# ORIONRP2350.net
KiCad netlist of a schematic drawn in EasyEDA
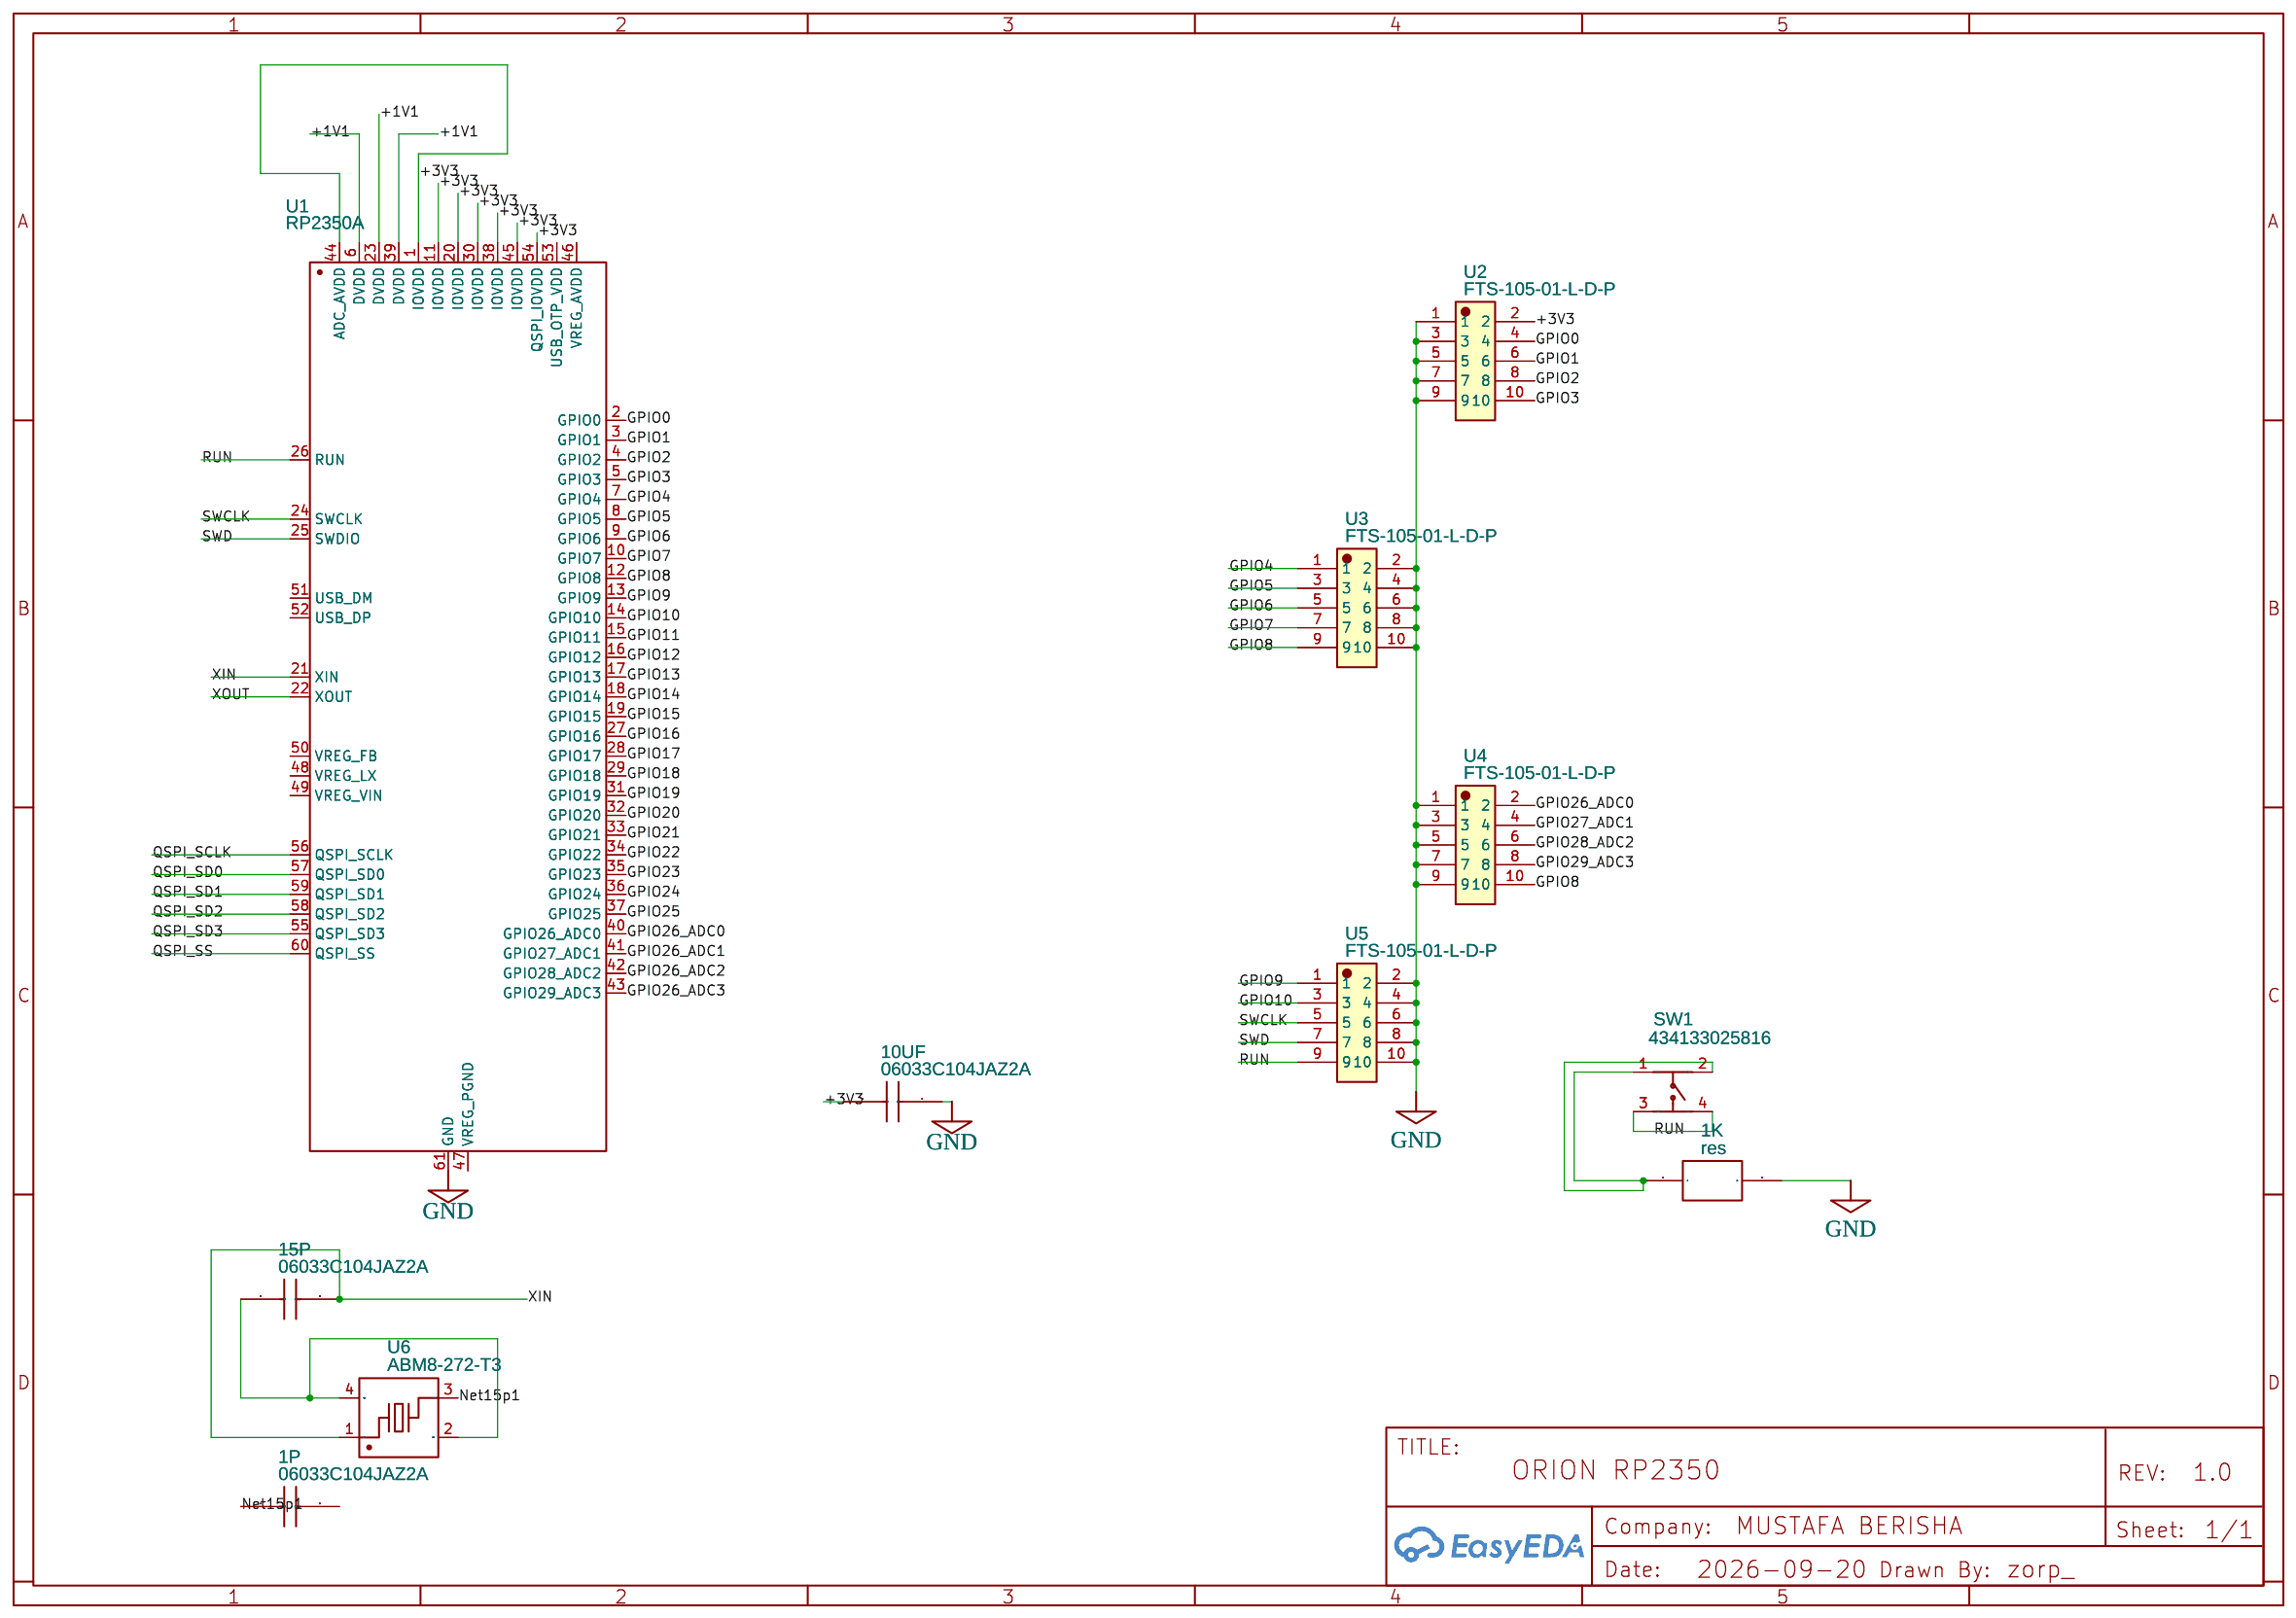
[diagram p0: schematic sheet]

(export (version "E")
  (design (tool "Eeschema 10.0.6"))
  (components
    (comp (ref "1K") (value "res") (libsource (lib "") (part "res")))
    (comp (ref "1P") (value "06033C104JAZ2A") (libsource (lib "") (part "06033C104JAZ2A")))
    (comp (ref "10UF") (value "06033C104JAZ2A") (libsource (lib "") (part "06033C104JAZ2A_1")))
    (comp (ref "15P") (value "06033C104JAZ2A") (libsource (lib "") (part "06033C104JAZ2A_2")))
    (comp (ref "SW1")
      (value "434133025816")
      (fields (field (name "Manufacturer") "Wurth(伍尔特)"))
      (libsource (lib "") (part "434133025816"))
    )
    (comp (ref "U1") (value "RP2350A") (libsource (lib "") (part "RP2350A")))
    (comp (ref "U2") (value "FTS-105-01-L-D-P") (libsource (lib "") (part "FTS-105-01-L-D-P")))
    (comp (ref "U3") (value "FTS-105-01-L-D-P") (libsource (lib "") (part "FTS-105-01-L-D-P")))
    (comp (ref "U4") (value "FTS-105-01-L-D-P") (libsource (lib "") (part "FTS-105-01-L-D-P")))
    (comp (ref "U5") (value "FTS-105-01-L-D-P") (libsource (lib "") (part "FTS-105-01-L-D-P")))
    (comp (ref "U6") (value "ABM8-272-T3") (libsource (lib "") (part "ABM8-272-T3")))
  )
  (nets
    (net (code "1") (name "/+1V1") (class "Default")
      (node (ref "U1") (pin "23") (pinfunction "DVDD_23") (pintype "unspecified"))
      (node (ref "U1") (pin "39") (pinfunction "DVDD_39") (pintype "unspecified"))
      (node (ref "U1") (pin "6") (pinfunction "DVDD_6") (pintype "unspecified"))
    )
    (net (code "2") (name "/+3V3") (class "Default")
      (node (ref "10UF") (pin "1") (pinfunction "1_1") (pintype "unspecified"))
      (node (ref "U1") (pin "1") (pinfunction "IOVDD_1") (pintype "unspecified"))
      (node (ref "U1") (pin "11") (pinfunction "IOVDD_11") (pintype "unspecified"))
      (node (ref "U1") (pin "20") (pinfunction "IOVDD_20") (pintype "unspecified"))
      (node (ref "U1") (pin "30") (pinfunction "IOVDD_30") (pintype "unspecified"))
      (node (ref "U1") (pin "38") (pinfunction "IOVDD_38") (pintype "unspecified"))
      (node (ref "U1") (pin "44") (pinfunction "ADC_AVDD_44") (pintype "unspecified"))
      (node (ref "U1") (pin "45") (pinfunction "IOVDD_45") (pintype "unspecified"))
      (node (ref "U1") (pin "54") (pinfunction "QSPI_IOVDD_54") (pintype "unspecified"))
      (node (ref "U2") (pin "2") (pinfunction "2_2") (pintype "unspecified"))
    )
    (net (code "3") (name "/GPIO0") (class "Default")
      (node (ref "U1") (pin "2") (pinfunction "GPIO0_2") (pintype "unspecified"))
      (node (ref "U2") (pin "4") (pinfunction "4_4") (pintype "unspecified"))
    )
    (net (code "4") (name "/GPIO1") (class "Default")
      (node (ref "U1") (pin "3") (pinfunction "GPIO1_3") (pintype "unspecified"))
      (node (ref "U2") (pin "6") (pinfunction "6_6") (pintype "unspecified"))
    )
    (net (code "5") (name "/GPIO2") (class "Default")
      (node (ref "U1") (pin "4") (pinfunction "GPIO2_4") (pintype "unspecified"))
      (node (ref "U2") (pin "8") (pinfunction "8_8") (pintype "unspecified"))
    )
    (net (code "6") (name "/GPIO3") (class "Default")
      (node (ref "U1") (pin "5") (pinfunction "GPIO3_5") (pintype "unspecified"))
      (node (ref "U2") (pin "10") (pinfunction "10_10") (pintype "unspecified"))
    )
    (net (code "7") (name "/GPIO4") (class "Default")
      (node (ref "U1") (pin "7") (pinfunction "GPIO4_7") (pintype "unspecified"))
      (node (ref "U3") (pin "1") (pinfunction "1_1") (pintype "unspecified"))
    )
    (net (code "8") (name "/GPIO5") (class "Default")
      (node (ref "U1") (pin "8") (pinfunction "GPIO5_8") (pintype "unspecified"))
      (node (ref "U3") (pin "3") (pinfunction "3_3") (pintype "unspecified"))
    )
    (net (code "9") (name "/GPIO6") (class "Default")
      (node (ref "U1") (pin "9") (pinfunction "GPIO6_9") (pintype "unspecified"))
      (node (ref "U3") (pin "5") (pinfunction "5_5") (pintype "unspecified"))
    )
    (net (code "10") (name "/GPIO7") (class "Default")
      (node (ref "U1") (pin "10") (pinfunction "GPIO7_10") (pintype "unspecified"))
      (node (ref "U3") (pin "7") (pinfunction "7_7") (pintype "unspecified"))
    )
    (net (code "11") (name "/GPIO8") (class "Default")
      (node (ref "U1") (pin "12") (pinfunction "GPIO8_12") (pintype "unspecified"))
      (node (ref "U3") (pin "9") (pinfunction "9_9") (pintype "unspecified"))
      (node (ref "U4") (pin "10") (pinfunction "10_10") (pintype "unspecified"))
    )
    (net (code "12") (name "/GPIO9") (class "Default")
      (node (ref "U1") (pin "13") (pinfunction "GPIO9_13") (pintype "unspecified"))
      (node (ref "U5") (pin "1") (pinfunction "1_1") (pintype "unspecified"))
    )
    (net (code "13") (name "/GPIO10") (class "Default")
      (node (ref "U1") (pin "14") (pinfunction "GPIO10_14") (pintype "unspecified"))
      (node (ref "U5") (pin "3") (pinfunction "3_3") (pintype "unspecified"))
    )
    (net (code "14") (name "/GPIO11") (class "Default")
      (node (ref "U1") (pin "15") (pinfunction "GPIO11_15") (pintype "unspecified"))
    )
    (net (code "15") (name "/GPIO12") (class "Default")
      (node (ref "U1") (pin "16") (pinfunction "GPIO12_16") (pintype "unspecified"))
    )
    (net (code "16") (name "/GPIO13") (class "Default")
      (node (ref "U1") (pin "17") (pinfunction "GPIO13_17") (pintype "unspecified"))
    )
    (net (code "17") (name "/GPIO14") (class "Default")
      (node (ref "U1") (pin "18") (pinfunction "GPIO14_18") (pintype "unspecified"))
    )
    (net (code "18") (name "/GPIO15") (class "Default")
      (node (ref "U1") (pin "19") (pinfunction "GPIO15_19") (pintype "unspecified"))
    )
    (net (code "19") (name "/GPIO16") (class "Default")
      (node (ref "U1") (pin "27") (pinfunction "GPIO16_27") (pintype "unspecified"))
    )
    (net (code "20") (name "/GPIO17") (class "Default")
      (node (ref "U1") (pin "28") (pinfunction "GPIO17_28") (pintype "unspecified"))
    )
    (net (code "21") (name "/GPIO18") (class "Default")
      (node (ref "U1") (pin "29") (pinfunction "GPIO18_29") (pintype "unspecified"))
    )
    (net (code "22") (name "/GPIO19") (class "Default")
      (node (ref "U1") (pin "31") (pinfunction "GPIO19_31") (pintype "unspecified"))
    )
    (net (code "23") (name "/GPIO20") (class "Default")
      (node (ref "U1") (pin "32") (pinfunction "GPIO20_32") (pintype "unspecified"))
    )
    (net (code "24") (name "/GPIO21") (class "Default")
      (node (ref "U1") (pin "33") (pinfunction "GPIO21_33") (pintype "unspecified"))
    )
    (net (code "25") (name "/GPIO22") (class "Default")
      (node (ref "U1") (pin "34") (pinfunction "GPIO22_34") (pintype "unspecified"))
    )
    (net (code "26") (name "/GPIO23") (class "Default")
      (node (ref "U1") (pin "35") (pinfunction "GPIO23_35") (pintype "unspecified"))
    )
    (net (code "27") (name "/GPIO24") (class "Default")
      (node (ref "U1") (pin "36") (pinfunction "GPIO24_36") (pintype "unspecified"))
    )
    (net (code "28") (name "/GPIO25") (class "Default")
      (node (ref "U1") (pin "37") (pinfunction "GPIO25_37") (pintype "unspecified"))
    )
    (net (code "29") (name "/GPIO26_ADC0") (class "Default")
      (node (ref "U1") (pin "40") (pinfunction "GPIO26_ADC0_40") (pintype "unspecified"))
      (node (ref "U4") (pin "2") (pinfunction "2_2") (pintype "unspecified"))
    )
    (net (code "30") (name "/GPIO26_ADC1") (class "Default")
      (node (ref "U1") (pin "41") (pinfunction "GPIO27_ADC1_41") (pintype "unspecified"))
    )
    (net (code "31") (name "/GPIO26_ADC2") (class "Default")
      (node (ref "U1") (pin "42") (pinfunction "GPIO28_ADC2_42") (pintype "unspecified"))
    )
    (net (code "32") (name "/GPIO26_ADC3") (class "Default")
      (node (ref "U1") (pin "43") (pinfunction "GPIO29_ADC3_43") (pintype "unspecified"))
    )
    (net (code "33") (name "/GPIO27_ADC1") (class "Default")
      (node (ref "U4") (pin "4") (pinfunction "4_4") (pintype "unspecified"))
    )
    (net (code "34") (name "/GPIO28_ADC2") (class "Default")
      (node (ref "U4") (pin "6") (pinfunction "6_6") (pintype "unspecified"))
    )
    (net (code "35") (name "/GPIO29_ADC3") (class "Default")
      (node (ref "U4") (pin "8") (pinfunction "8_8") (pintype "unspecified"))
    )
    (net (code "36") (name "/Net15p1") (class "Default")
      (node (ref "1P") (pin "1") (pinfunction "1_1") (pintype "unspecified"))
      (node (ref "U6") (pin "3") (pinfunction "3_3") (pintype "input"))
    )
    (net (code "37") (name "/QSPI_SCLK") (class "Default")
      (node (ref "U1") (pin "56") (pinfunction "QSPI_SCLK_56") (pintype "unspecified"))
    )
    (net (code "38") (name "/QSPI_SD0") (class "Default")
      (node (ref "U1") (pin "57") (pinfunction "QSPI_SD0_57") (pintype "unspecified"))
    )
    (net (code "39") (name "/QSPI_SD1") (class "Default")
      (node (ref "U1") (pin "59") (pinfunction "QSPI_SD1_59") (pintype "unspecified"))
    )
    (net (code "40") (name "/QSPI_SD2") (class "Default")
      (node (ref "U1") (pin "58") (pinfunction "QSPI_SD2_58") (pintype "unspecified"))
    )
    (net (code "41") (name "/QSPI_SD3") (class "Default")
      (node (ref "U1") (pin "55") (pinfunction "QSPI_SD3_55") (pintype "unspecified"))
    )
    (net (code "42") (name "/QSPI_SS") (class "Default")
      (node (ref "U1") (pin "60") (pinfunction "QSPI_SS_60") (pintype "unspecified"))
    )
    (net (code "43") (name "/RUN") (class "Default")
      (node (ref "SW1") (pin "3") (pinfunction "3_3") (pintype "unspecified"))
      (node (ref "SW1") (pin "4") (pinfunction "4_4") (pintype "unspecified"))
      (node (ref "U1") (pin "26") (pinfunction "RUN_26") (pintype "unspecified"))
      (node (ref "U5") (pin "9") (pinfunction "9_9") (pintype "unspecified"))
    )
    (net (code "44") (name "/SWCLK") (class "Default")
      (node (ref "U1") (pin "24") (pinfunction "SWCLK_24") (pintype "unspecified"))
      (node (ref "U5") (pin "5") (pinfunction "5_5") (pintype "unspecified"))
    )
    (net (code "45") (name "/SWD") (class "Default")
      (node (ref "U1") (pin "25") (pinfunction "SWDIO_25") (pintype "unspecified"))
      (node (ref "U5") (pin "7") (pinfunction "7_7") (pintype "unspecified"))
    )
    (net (code "46") (name "/XIN") (class "Default")
      (node (ref "15P") (pin "2") (pinfunction "2_2") (pintype "unspecified"))
      (node (ref "U1") (pin "21") (pinfunction "XIN_21") (pintype "unspecified"))
      (node (ref "U6") (pin "1") (pinfunction "1_1") (pintype "input"))
    )
    (net (code "47") (name "/XOUT") (class "Default")
      (node (ref "U1") (pin "22") (pinfunction "XOUT_22") (pintype "unspecified"))
    )
    (net (code "48") (name "GND") (class "Default")
      (node (ref "10UF") (pin "2") (pinfunction "2_2") (pintype "unspecified"))
      (node (ref "1K") (pin "2") (pinfunction "2_2") (pintype "unspecified"))
      (node (ref "U1") (pin "61") (pinfunction "GND_61") (pintype "unspecified"))
      (node (ref "U2") (pin "1") (pinfunction "1_1") (pintype "unspecified"))
      (node (ref "U2") (pin "3") (pinfunction "3_3") (pintype "unspecified"))
      (node (ref "U2") (pin "5") (pinfunction "5_5") (pintype "unspecified"))
      (node (ref "U2") (pin "7") (pinfunction "7_7") (pintype "unspecified"))
      (node (ref "U2") (pin "9") (pinfunction "9_9") (pintype "unspecified"))
      (node (ref "U3") (pin "10") (pinfunction "10_10") (pintype "unspecified"))
      (node (ref "U3") (pin "2") (pinfunction "2_2") (pintype "unspecified"))
      (node (ref "U3") (pin "4") (pinfunction "4_4") (pintype "unspecified"))
      (node (ref "U3") (pin "6") (pinfunction "6_6") (pintype "unspecified"))
      (node (ref "U3") (pin "8") (pinfunction "8_8") (pintype "unspecified"))
      (node (ref "U4") (pin "1") (pinfunction "1_1") (pintype "unspecified"))
      (node (ref "U4") (pin "3") (pinfunction "3_3") (pintype "unspecified"))
      (node (ref "U4") (pin "5") (pinfunction "5_5") (pintype "unspecified"))
      (node (ref "U4") (pin "7") (pinfunction "7_7") (pintype "unspecified"))
      (node (ref "U4") (pin "9") (pinfunction "9_9") (pintype "unspecified"))
      (node (ref "U5") (pin "10") (pinfunction "10_10") (pintype "unspecified"))
      (node (ref "U5") (pin "2") (pinfunction "2_2") (pintype "unspecified"))
      (node (ref "U5") (pin "4") (pinfunction "4_4") (pintype "unspecified"))
      (node (ref "U5") (pin "6") (pinfunction "6_6") (pintype "unspecified"))
      (node (ref "U5") (pin "8") (pinfunction "8_8") (pintype "unspecified"))
    )
    (net (code "49") (name "Net-(1K-Pad1)") (class "Default")
      (node (ref "1K") (pin "1") (pinfunction "1_1") (pintype "unspecified"))
      (node (ref "SW1") (pin "1") (pinfunction "1_1") (pintype "unspecified"))
      (node (ref "SW1") (pin "2") (pinfunction "2_2") (pintype "unspecified"))
    )
    (net (code "50") (name "Net-(15P-Pad1)") (class "Default")
      (node (ref "15P") (pin "1") (pinfunction "1_1") (pintype "unspecified"))
      (node (ref "U6") (pin "2") (pinfunction "GND_2") (pintype "input"))
      (node (ref "U6") (pin "4") (pinfunction "GND_4") (pintype "input"))
    )
    (net (code "51") (name "unconnected-(1P-Pad2)") (class "Default")
      (node (ref "1P") (pin "2") (pinfunction "2_2") (pintype "unspecified"))
    )
    (net (code "52") (name "unconnected-(U1-USB_DM-Pad51)") (class "Default")
      (node (ref "U1") (pin "51") (pinfunction "USB_DM_51") (pintype "unspecified"))
    )
    (net (code "53") (name "unconnected-(U1-USB_DP-Pad52)") (class "Default")
      (node (ref "U1") (pin "52") (pinfunction "USB_DP_52") (pintype "unspecified"))
    )
    (net (code "54") (name "unconnected-(U1-USB_OTP_VDD-Pad53)") (class "Default")
      (node (ref "U1") (pin "53") (pinfunction "USB_OTP_VDD_53") (pintype "unspecified"))
    )
    (net (code "55") (name "unconnected-(U1-VREG_AVDD-Pad46)") (class "Default")
      (node (ref "U1") (pin "46") (pinfunction "VREG_AVDD_46") (pintype "unspecified"))
    )
    (net (code "56") (name "unconnected-(U1-VREG_FB-Pad50)") (class "Default")
      (node (ref "U1") (pin "50") (pinfunction "VREG_FB_50") (pintype "unspecified"))
    )
    (net (code "57") (name "unconnected-(U1-VREG_LX-Pad48)") (class "Default")
      (node (ref "U1") (pin "48") (pinfunction "VREG_LX_48") (pintype "unspecified"))
    )
    (net (code "58") (name "unconnected-(U1-VREG_PGND-Pad47)") (class "Default")
      (node (ref "U1") (pin "47") (pinfunction "VREG_PGND_47") (pintype "unspecified"))
    )
    (net (code "59") (name "unconnected-(U1-VREG_VIN-Pad49)") (class "Default")
      (node (ref "U1") (pin "49") (pinfunction "VREG_VIN_49") (pintype "unspecified"))
    )
  )
)
